# TDFC_V2_0_Black_10by10_1_6mm_ENIG_10pcs.net
KiCad netlist of a schematic drawn in EAGLE
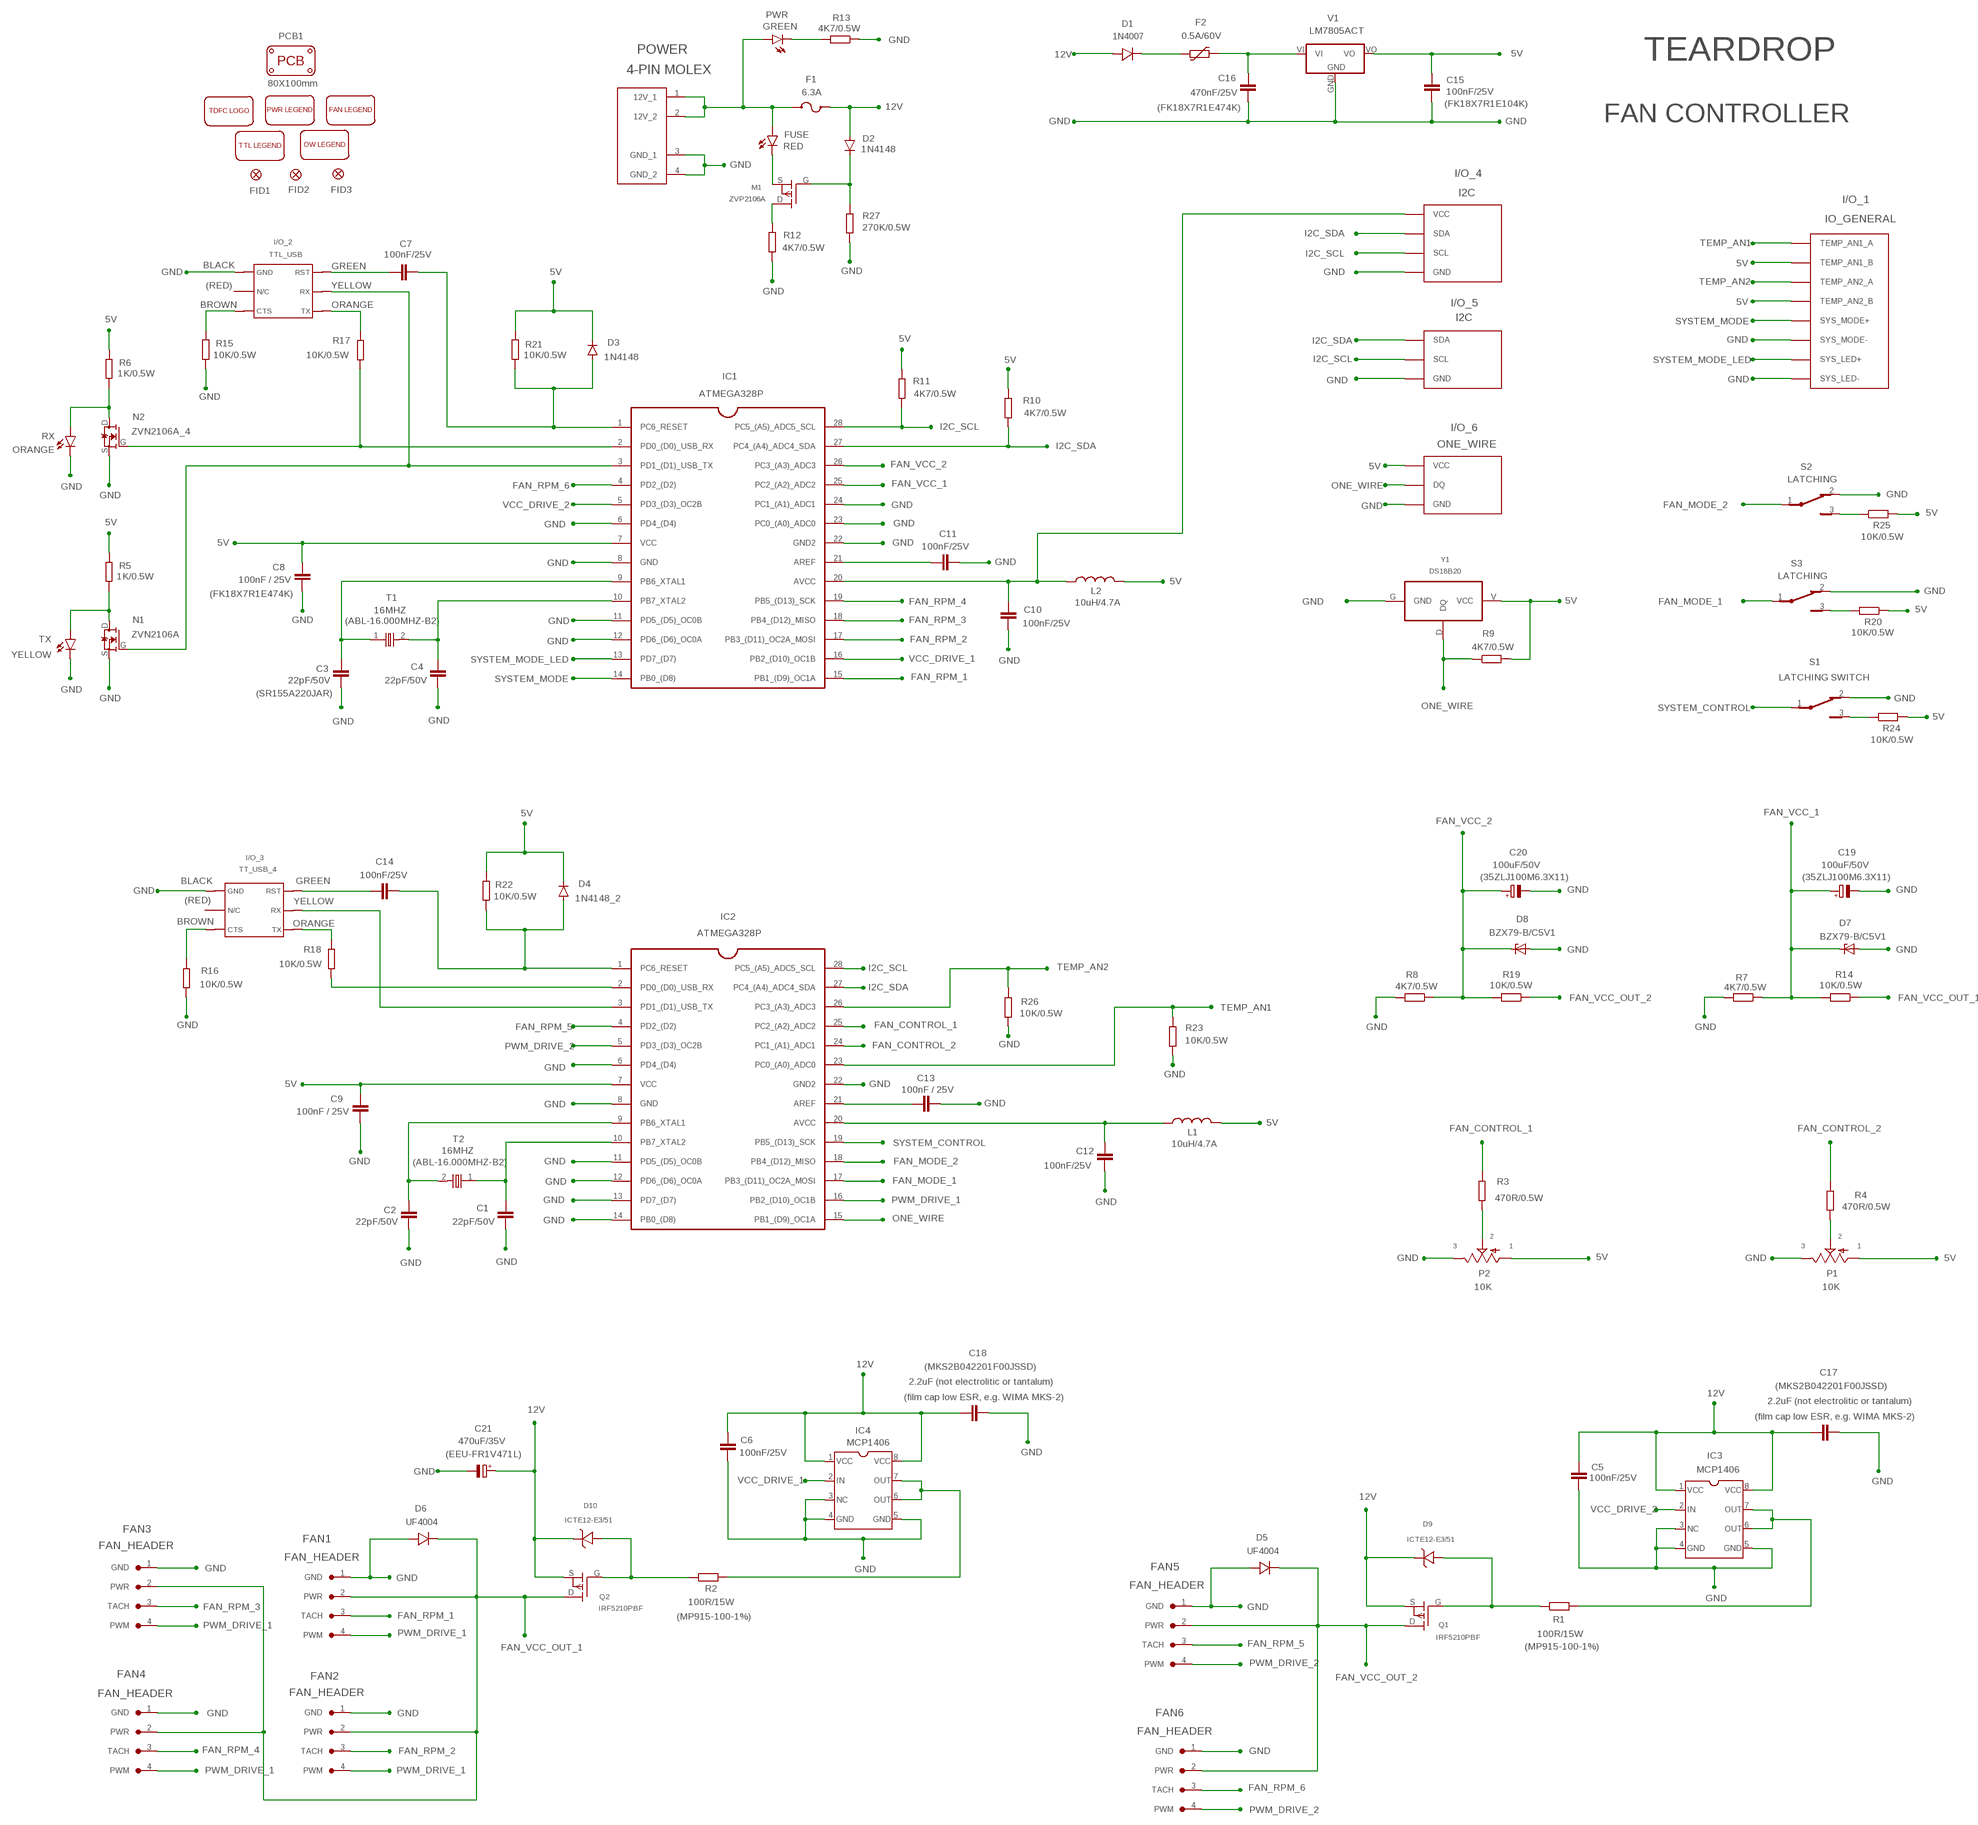
[diagram p0: schematic, sheet 1]

(export (version "E")
  (design (tool "Eeschema 10.0.6"))
  (components
    (comp (ref "C1")
      (value "22pF/50V")
      (footprint "eagle-import:MLCC_CERAMIC_9")
      (libsource (lib "eagle-import") (part "MLCC_CERAMIC_9"))
    )
    (comp (ref "C2")
      (value "22pF/50V")
      (footprint "eagle-import:MLCC_CERAMIC_9")
      (libsource (lib "eagle-import") (part "MLCC_CERAMIC_9"))
    )
    (comp (ref "C3")
      (value "22pF/50V")
      (footprint "eagle-import:MLCC_CERAMIC_11")
      (libsource (lib "eagle-import") (part "MLCC_CERAMIC_11"))
    )
    (comp (ref "C4")
      (value "22pF/50V")
      (footprint "eagle-import:MLCC_CERAMIC_11")
      (libsource (lib "eagle-import") (part "MLCC_CERAMIC_11"))
    )
    (comp (ref "C5")
      (value "100nF/25V")
      (footprint "eagle-import:MLCC_CERAMIC_5")
      (libsource (lib "eagle-import") (part "MLCC_CERAMIC_5"))
    )
    (comp (ref "C6")
      (value "100nF/25V")
      (footprint "eagle-import:MLCC_CERAMIC_5")
      (libsource (lib "eagle-import") (part "MLCC_CERAMIC_5"))
    )
    (comp (ref "C7")
      (value "100nF/25V")
      (footprint "eagle-import:MLCC_CERAMIC_7")
      (libsource (lib "eagle-import") (part "MLCC_CERAMIC_7"))
    )
    (comp (ref "C8")
      (value "100nF / 25V")
      (footprint "eagle-import:MLCC_CERAMIC_5")
      (libsource (lib "eagle-import") (part "MLCC_CERAMIC_5"))
    )
    (comp (ref "C9")
      (value "100nF / 25V")
      (footprint "eagle-import:MLCC_CERAMIC_5")
      (libsource (lib "eagle-import") (part "MLCC_CERAMIC_5"))
    )
    (comp (ref "C10")
      (value "100nF/25V")
      (footprint "eagle-import:MLCC_CERAMIC")
      (libsource (lib "eagle-import") (part "MLCC_CERAMIC"))
    )
    (comp (ref "C11")
      (value "100nF/25V")
      (footprint "eagle-import:MLCC_CERAMIC_17")
      (libsource (lib "eagle-import") (part "MLCC_CERAMIC_17"))
    )
    (comp (ref "C12")
      (value "100nF/25V")
      (footprint "eagle-import:MLCC_CERAMIC_6")
      (libsource (lib "eagle-import") (part "MLCC_CERAMIC_6"))
    )
    (comp (ref "C13")
      (value "100nF / 25V")
      (footprint "eagle-import:MLCC_CERAMIC_6")
      (libsource (lib "eagle-import") (part "MLCC_CERAMIC_6"))
    )
    (comp (ref "C14")
      (value "100nF/25V")
      (footprint "eagle-import:MLCC_CERAMIC_14")
      (libsource (lib "eagle-import") (part "MLCC_CERAMIC_14"))
    )
    (comp (ref "C15")
      (value "100nF/25V")
      (footprint "eagle-import:MLCC_CERAMIC_16")
      (libsource (lib "eagle-import") (part "MLCC_CERAMIC_16"))
    )
    (comp (ref "C16")
      (value "470nF/25V")
      (footprint "eagle-import:MLCC_CERAMIC_15")
      (libsource (lib "eagle-import") (part "MLCC_CERAMIC_15"))
    )
    (comp (ref "C17")
      (value "(MKS2B042201F00JSSD)")
      (footprint "eagle-import:WIMA_CAPACITOR_2")
      (libsource (lib "eagle-import") (part "WIMA_CAPACITOR_2"))
    )
    (comp (ref "C18")
      (value "(MKS2B042201F00JSSD)")
      (footprint "eagle-import:WIMA_CAPACITOR_2")
      (libsource (lib "eagle-import") (part "WIMA_CAPACITOR_2"))
    )
    (comp (ref "C19")
      (value "100uF/50V")
      (footprint "eagle-import:CAPACITOR_6.3_RIGHT")
      (libsource (lib "eagle-import") (part "CAPACITOR_6.3_RIGHT"))
    )
    (comp (ref "C20")
      (value "100uF/50V")
      (footprint "eagle-import:CAPACITOR_6.3_RIGHT")
      (libsource (lib "eagle-import") (part "CAPACITOR_6.3_RIGHT"))
    )
    (comp (ref "C21")
      (value "470uF/35V")
      (footprint "eagle-import:ELECTROLYTIC_CAPACITOR_RIGHT")
      (libsource (lib "eagle-import") (part "ELECTROLYTIC_CAPACITOR_RIGHT"))
    )
    (comp (ref "D1")
      (value "1N4007")
      (footprint "eagle-import:UF4004")
      (libsource (lib "eagle-import") (part "UF4004"))
    )
    (comp (ref "D2")
      (value "1N4148")
      (footprint "eagle-import:1N4148")
      (libsource (lib "eagle-import") (part "1N4148"))
    )
    (comp (ref "D3")
      (value "1N4148")
      (footprint "eagle-import:1N4148")
      (libsource (lib "eagle-import") (part "1N4148"))
    )
    (comp (ref "D4")
      (value "1N4148_2")
      (footprint "eagle-import:1N4148_2")
      (libsource (lib "eagle-import") (part "1N4148_2"))
    )
    (comp (ref "D5")
      (value "UF4004")
      (footprint "eagle-import:UF4004_2")
      (libsource (lib "eagle-import") (part "UF4004_2"))
    )
    (comp (ref "D6")
      (value "UF4004")
      (footprint "eagle-import:UF4004_2")
      (libsource (lib "eagle-import") (part "UF4004_2"))
    )
    (comp (ref "D7")
      (value "BZX79-B/C5V1")
      (footprint "eagle-import:DO34_2")
      (libsource (lib "eagle-import") (part "BZX90_2"))
    )
    (comp (ref "D8")
      (value "BZX79-B/C5V1")
      (footprint "eagle-import:DO34Z7")
      (libsource (lib "eagle-import") (part "BZX90"))
    )
    (comp (ref "D9")
      (value "ICTE12-E3/51")
      (footprint "eagle-import:TVS_DIODE_5")
      (libsource (lib "eagle-import") (part "TVS_DIODE_5"))
    )
    (comp (ref "D10")
      (value "ICTE12-E3/51")
      (footprint "eagle-import:TVS_DIODE_5")
      (libsource (lib "eagle-import") (part "TVS_DIODE_5"))
    )
    (comp (ref "F1")
      (value "6.3A")
      (footprint "eagle-import:FUSE_GLASS")
      (libsource (lib "eagle-import") (part "FUSE_GLASS"))
    )
    (comp (ref "F2")
      (value "0.5A/60V")
      (footprint "eagle-import:PTC")
      (libsource (lib "eagle-import") (part "PTC"))
    )
    (comp (ref "FAN1")
      (value "FAN_HEADER")
      (footprint "eagle-import:4PIN_FAN_HEADER")
      (libsource (lib "eagle-import") (part "4PIN_FAN_HEADER"))
    )
    (comp (ref "FAN2")
      (value "FAN_HEADER")
      (footprint "eagle-import:4PIN_FAN_HEADER")
      (libsource (lib "eagle-import") (part "4PIN_FAN_HEADER"))
    )
    (comp (ref "FAN3")
      (value "FAN_HEADER")
      (footprint "eagle-import:4PIN_FAN_HEADER")
      (libsource (lib "eagle-import") (part "4PIN_FAN_HEADER"))
    )
    (comp (ref "FAN4")
      (value "FAN_HEADER")
      (footprint "eagle-import:4PIN_FAN_HEADER")
      (libsource (lib "eagle-import") (part "4PIN_FAN_HEADER"))
    )
    (comp (ref "FAN5")
      (value "FAN_HEADER")
      (footprint "eagle-import:4PIN_FAN_HEADER")
      (libsource (lib "eagle-import") (part "4PIN_FAN_HEADER"))
    )
    (comp (ref "FAN6")
      (value "FAN_HEADER")
      (footprint "eagle-import:4PIN_FAN_HEADER")
      (libsource (lib "eagle-import") (part "4PIN_FAN_HEADER"))
    )
    (comp (ref "FID1")
      (value "FIDUCIAL1X2")
      (footprint "eagle-import:FIDUCIAL-1X2")
      (libsource (lib "eagle-import") (part "FIDUCIAL1X2"))
    )
    (comp (ref "FID2")
      (value "FIDUCIAL1X2")
      (footprint "eagle-import:FIDUCIAL-1X2")
      (libsource (lib "eagle-import") (part "FIDUCIAL1X2"))
    )
    (comp (ref "FID3")
      (value "FIDUCIAL1X2")
      (footprint "eagle-import:FIDUCIAL-1X2")
      (libsource (lib "eagle-import") (part "FIDUCIAL1X2"))
    )
    (comp (ref "FUSE")
      (value "RED")
      (footprint "eagle-import:LED_1.8_LEFT")
      (libsource (lib "eagle-import") (part "LED_1.8_LEFT"))
    )
    (comp (ref "I/O_1")
      (value "IO_GENERAL")
      (footprint "eagle-import:IO_GENERAL_7")
      (libsource (lib "eagle-import") (part "IO_GENERAL_7"))
    )
    (comp (ref "I/O_2")
      (value "TTL_USB")
      (footprint "eagle-import:TTL_USB_5")
      (libsource (lib "eagle-import") (part "TTL_USB_5"))
    )
    (comp (ref "I/O_3")
      (value "TT_USB_4")
      (footprint "eagle-import:TT_USB_4")
      (libsource (lib "eagle-import") (part "TT_USB_4"))
    )
    (comp (ref "I/O_4")
      (value "I2C")
      (footprint "eagle-import:4_PIN_HEADER_VERTICAL_2")
      (libsource (lib "eagle-import") (part "4_PIN_HEADER_VERTICAL_2"))
    )
    (comp (ref "I/O_5")
      (value "I2C")
      (footprint "eagle-import:3_PIN_VERTICAL_4")
      (libsource (lib "eagle-import") (part "3_PIN_VERTICAL_4"))
    )
    (comp (ref "I/O_6")
      (value "ONE_WIRE")
      (footprint "eagle-import:3_PIN_VERTICAL")
      (libsource (lib "eagle-import") (part "3_PIN_VERTICAL"))
    )
    (comp (ref "IC1")
      (value "ATMEGA328P")
      (footprint "eagle-import:ATMEGA328P")
      (libsource (lib "eagle-import") (part "ATMEGA328P"))
    )
    (comp (ref "IC2")
      (value "ATMEGA328P")
      (footprint "eagle-import:ATMEGA328P_2")
      (libsource (lib "eagle-import") (part "ATMEGA328P_VER_2.0"))
    )
    (comp (ref "IC3")
      (value "MCP1406")
      (footprint "eagle-import:TC4420")
      (libsource (lib "eagle-import") (part "TC4420"))
    )
    (comp (ref "IC4")
      (value "MCP1406")
      (footprint "eagle-import:TC4420")
      (libsource (lib "eagle-import") (part "TC4420"))
    )
    (comp (ref "L1")
      (value "10uH/4.7A")
      (footprint "eagle-import:INDUCTOR")
      (libsource (lib "eagle-import") (part "INDUCTOR"))
    )
    (comp (ref "L2")
      (value "10uH/4.7A")
      (footprint "eagle-import:INDUCTOR")
      (libsource (lib "eagle-import") (part "INDUCTOR"))
    )
    (comp (ref "M1")
      (value "ZVP2106A")
      (footprint "eagle-import:ZVP2106A")
      (libsource (lib "eagle-import") (part "ZVP2106A"))
    )
    (comp (ref "N1")
      (value "ZVN2106A")
      (footprint "eagle-import:ZVN2106A")
      (libsource (lib "eagle-import") (part "ZVN2106A"))
    )
    (comp (ref "N2")
      (value "ZVN2106A_4")
      (footprint "eagle-import:ZVN2106A_4")
      (libsource (lib "eagle-import") (part "ZVN2106A_4"))
    )
    (comp (ref "P1")
      (value "10K")
      (footprint "eagle-import:POTENTIMETER_SQUARE")
      (libsource (lib "eagle-import") (part "POTENTIMETER_SQUARE"))
    )
    (comp (ref "P2")
      (value "10K")
      (footprint "eagle-import:POTENTIMETER_SQUARE")
      (libsource (lib "eagle-import") (part "POTENTIMETER_SQUARE"))
    )
    (comp (ref "PCB1")
      (value "80X100mm")
      (footprint "eagle-import:DP10080_V1")
      (libsource (lib "eagle-import") (part "PCB_DP_RECTANGLE-80X100"))
    )
    (comp (ref "POWER")
      (value "4-PIN MOLEX")
      (footprint "eagle-import:MOLEX_4PIN_2")
      (libsource (lib "eagle-import") (part "MOLEX_4PIN_2"))
    )
    (comp (ref "PWR")
      (value "GREEN")
      (footprint "eagle-import:LED_1.8_LEFT")
      (libsource (lib "eagle-import") (part "LED_1.8_LEFT"))
    )
    (comp (ref "Q1")
      (value "IRF5210PBF")
      (footprint "eagle-import:IRF5210")
      (libsource (lib "eagle-import") (part "IRF5210"))
    )
    (comp (ref "Q2")
      (value "IRF5210PBF")
      (footprint "eagle-import:IRF5210")
      (libsource (lib "eagle-import") (part "IRF5210"))
    )
    (comp (ref "R1")
      (value "100R/15W")
      (footprint "eagle-import:V234_12")
      (libsource (lib "eagle-import") (part "R-EU_V234/12"))
    )
    (comp (ref "R2")
      (value "100R/15W")
      (footprint "eagle-import:V234_12")
      (libsource (lib "eagle-import") (part "R-EU_V234/12"))
    )
    (comp (ref "R3")
      (value "470R/0.5W")
      (footprint "eagle-import:0204_5")
      (libsource (lib "eagle-import") (part "RESISTOR (REGULAR, 0.25W)_R-EU_0204/5"))
    )
    (comp (ref "R4")
      (value "470R/0.5W")
      (footprint "eagle-import:0204_5")
      (libsource (lib "eagle-import") (part "RESISTOR (REGULAR, 0.25W)_R-EU_0204/5"))
    )
    (comp (ref "R5")
      (value "1K/0.5W")
      (footprint "eagle-import:0204_5")
      (libsource (lib "eagle-import") (part "RESISTOR (REGULAR, 0.25W)_R-EU_0204/5"))
    )
    (comp (ref "R6")
      (value "1K/0.5W")
      (footprint "eagle-import:0204_5")
      (libsource (lib "eagle-import") (part "RESISTOR (REGULAR, 0.25W)_R-EU_0204/5"))
    )
    (comp (ref "R7")
      (value "4K7/0.5W")
      (footprint "eagle-import:0204_5")
      (libsource (lib "eagle-import") (part "RESISTOR (REGULAR, 0.25W)_R-EU_0204/5"))
    )
    (comp (ref "R8")
      (value "4K7/0.5W")
      (footprint "eagle-import:0204_5")
      (libsource (lib "eagle-import") (part "RESISTOR (REGULAR, 0.25W)_R-EU_0204/5"))
    )
    (comp (ref "R9")
      (value "4K7/0.5W")
      (footprint "eagle-import:0204_5")
      (libsource (lib "eagle-import") (part "RESISTOR (REGULAR, 0.25W)_R-EU_0204/5"))
    )
    (comp (ref "R10")
      (value "4K7/0.5W")
      (footprint "eagle-import:0204_5")
      (libsource (lib "eagle-import") (part "RESISTOR (REGULAR, 0.25W)_R-EU_0204/5"))
    )
    (comp (ref "R11")
      (value "4K7/0.5W")
      (footprint "eagle-import:0204_5")
      (libsource (lib "eagle-import") (part "RESISTOR (REGULAR, 0.25W)_R-EU_0204/5"))
    )
    (comp (ref "R12")
      (value "4K7/0.5W")
      (footprint "eagle-import:0204_5")
      (libsource (lib "eagle-import") (part "RESISTOR (REGULAR, 0.25W)_R-EU_0204/5"))
    )
    (comp (ref "R13")
      (value "4K7/0.5W")
      (footprint "eagle-import:0204_5")
      (libsource (lib "eagle-import") (part "RESISTOR (REGULAR, 0.25W)_R-EU_0204/5"))
    )
    (comp (ref "R14")
      (value "10K/0.5W")
      (footprint "eagle-import:0204_5")
      (libsource (lib "eagle-import") (part "RESISTOR (REGULAR, 0.25W)_R-EU_0204/5"))
    )
    (comp (ref "R15")
      (value "10K/0.5W")
      (footprint "eagle-import:0204_5")
      (libsource (lib "eagle-import") (part "RESISTOR (REGULAR, 0.25W)_R-EU_0204/5"))
    )
    (comp (ref "R16")
      (value "10K/0.5W")
      (footprint "eagle-import:0204_5")
      (libsource (lib "eagle-import") (part "RESISTOR (REGULAR, 0.25W)_R-EU_0204/5"))
    )
    (comp (ref "R17")
      (value "10K/0.5W")
      (footprint "eagle-import:0204_5")
      (libsource (lib "eagle-import") (part "RESISTOR (REGULAR, 0.25W)_R-EU_0204/5"))
    )
    (comp (ref "R18")
      (value "10K/0.5W")
      (footprint "eagle-import:0204_5")
      (libsource (lib "eagle-import") (part "RESISTOR (REGULAR, 0.25W)_R-EU_0204/5"))
    )
    (comp (ref "R19")
      (value "10K/0.5W")
      (footprint "eagle-import:0204_5")
      (libsource (lib "eagle-import") (part "RESISTOR (REGULAR, 0.25W)_R-EU_0204/5"))
    )
    (comp (ref "R20")
      (value "10K/0.5W")
      (footprint "eagle-import:0204_5")
      (libsource (lib "eagle-import") (part "RESISTOR (REGULAR, 0.25W)_R-EU_0204/5"))
    )
    (comp (ref "R21")
      (value "10K/0.5W")
      (footprint "eagle-import:0204_5")
      (libsource (lib "eagle-import") (part "RESISTOR (REGULAR, 0.25W)_R-EU_0204/5"))
    )
    (comp (ref "R22")
      (value "10K/0.5W")
      (footprint "eagle-import:0204_5")
      (libsource (lib "eagle-import") (part "RESISTOR (REGULAR, 0.25W)_R-EU_0204/5"))
    )
    (comp (ref "R23")
      (value "10K/0.5W")
      (footprint "eagle-import:0204_5")
      (libsource (lib "eagle-import") (part "RESISTOR (REGULAR, 0.25W)_R-EU_0204/5"))
    )
    (comp (ref "R24")
      (value "10K/0.5W")
      (footprint "eagle-import:0204_5")
      (libsource (lib "eagle-import") (part "RESISTOR (REGULAR, 0.25W)_R-EU_0204/5"))
    )
    (comp (ref "R25")
      (value "10K/0.5W")
      (footprint "eagle-import:0204_5")
      (libsource (lib "eagle-import") (part "RESISTOR (REGULAR, 0.25W)_R-EU_0204/5"))
    )
    (comp (ref "R26")
      (value "10K/0.5W")
      (footprint "eagle-import:0204_5")
      (libsource (lib "eagle-import") (part "RESISTOR (REGULAR, 0.25W)_R-EU_0204/5"))
    )
    (comp (ref "R27")
      (value "270K/0.5W")
      (footprint "eagle-import:0204_5")
      (libsource (lib "eagle-import") (part "RESISTOR (REGULAR, 0.25W)_R-EU_0204/5"))
    )
    (comp (ref "RX")
      (value "ORANGE")
      (footprint "eagle-import:LED_1.8_LEFT_2")
      (libsource (lib "eagle-import") (part "LED_1.8_LEFT_2"))
    )
    (comp (ref "S1")
      (value "LATCHING SWITCH")
      (footprint "eagle-import:SLIDING_SWITCH_4")
      (libsource (lib "eagle-import") (part "SLIDING_SWITCH_4"))
    )
    (comp (ref "S2")
      (value "LATCHING")
      (footprint "eagle-import:SLIDING_SWITCH_5")
      (libsource (lib "eagle-import") (part "SLIDING_SWITCH_5"))
    )
    (comp (ref "S3")
      (value "LATCHING")
      (footprint "eagle-import:SLIDING_SWITCH_5")
      (libsource (lib "eagle-import") (part "SLIDING_SWITCH_5"))
    )
    (comp (ref "T1")
      (value "16MHZ")
      (footprint "eagle-import:CRYSTAL_16MHZ")
      (libsource (lib "eagle-import") (part "CRYSTAL_16MHZ"))
    )
    (comp (ref "T2")
      (value "16MHZ")
      (footprint "eagle-import:CRYSTAL_16MHZ")
      (libsource (lib "eagle-import") (part "CRYSTAL_16MHZ"))
    )
    (comp (ref "TX")
      (value "YELLOW")
      (footprint "eagle-import:LED_1.8_LEFT_2")
      (libsource (lib "eagle-import") (part "LED_1.8_LEFT_2"))
    )
    (comp (ref "U$1")
      (value "TDFC_LOGO")
      (footprint "eagle-import:TDFC_LOGO")
      (libsource (lib "eagle-import") (part "TDFC_LOGO"))
    )
    (comp (ref "U$2")
      (value "MOLEX_4PIN_LEGEND_2")
      (footprint "eagle-import:MOLEX_4PIN_LEGEND_2")
      (libsource (lib "eagle-import") (part "MOLEX_4PIN_LEGEND_2"))
    )
    (comp (ref "U$3")
      (value "FAN_HEADER_LEGEND")
      (footprint "eagle-import:FAN_HEADER_LEGEND")
      (libsource (lib "eagle-import") (part "FAN_HEADER_LEGEND"))
    )
    (comp (ref "U$4")
      (value "TTL_USB_6")
      (footprint "eagle-import:TTL_USB_6")
      (libsource (lib "eagle-import") (part "TTL_USB_6"))
    )
    (comp (ref "U$5")
      (value "3_PIN_VERTICAL_LEGEND")
      (footprint "eagle-import:3_PIN_VERTICAL_LEGEND")
      (libsource (lib "eagle-import") (part "3_PIN_VERTICAL_LEGEND"))
    )
    (comp (ref "V1")
      (value "LM7805ACT")
      (footprint "eagle-import:LM7805")
      (libsource (lib "eagle-import") (part "LM7805"))
    )
    (comp (ref "Y1")
      (value "DS18B20")
      (footprint "eagle-import:DS18B20")
      (libsource (lib "eagle-import") (part "DS18B20"))
    )
  )
  (nets
    (net (code "1") (name "/5V") (class "Default")
      (node (ref "C15") (pin "2") (pinfunction "2_2") (pintype "passive"))
      (node (ref "C8") (pin "1") (pinfunction "1_1") (pintype "passive"))
      (node (ref "C9") (pin "1") (pinfunction "1_1") (pintype "passive"))
      (node (ref "D3") (pin "C") (pinfunction "C_C") (pintype "passive"))
      (node (ref "D4") (pin "C") (pinfunction "C_C") (pintype "passive"))
      (node (ref "I/O_1") (pin "TEMP_AN1_B") (pinfunction "TEMP_AN1_B_TEMP_AN1_B") (pintype "passive"))
      (node (ref "I/O_1") (pin "TEMP_AN2_B") (pinfunction "TEMP_AN2_B_TEMP_AN2_B") (pintype "passive"))
      (node (ref "I/O_6") (pin "VCC") (pinfunction "VCC_VCC") (pintype "passive"))
      (node (ref "IC1") (pin "7") (pinfunction "VCC_7") (pintype "bidirectional"))
      (node (ref "IC2") (pin "7") (pinfunction "VCC_7") (pintype "bidirectional"))
      (node (ref "L1") (pin "2") (pinfunction "2_2") (pintype "passive"))
      (node (ref "L2") (pin "2") (pinfunction "2_2") (pintype "passive"))
      (node (ref "P1") (pin "1") (pinfunction "A_1") (pintype "passive"))
      (node (ref "P2") (pin "1") (pinfunction "A_1") (pintype "passive"))
      (node (ref "R10") (pin "1") (pinfunction "1_1") (pintype "passive"))
      (node (ref "R11") (pin "1") (pinfunction "1_1") (pintype "passive"))
      (node (ref "R20") (pin "1") (pinfunction "1_1") (pintype "passive"))
      (node (ref "R21") (pin "2") (pinfunction "2_2") (pintype "passive"))
      (node (ref "R22") (pin "2") (pinfunction "2_2") (pintype "passive"))
      (node (ref "R24") (pin "2") (pinfunction "2_2") (pintype "passive"))
      (node (ref "R25") (pin "2") (pinfunction "2_2") (pintype "passive"))
      (node (ref "R5") (pin "2") (pinfunction "2_2") (pintype "passive"))
      (node (ref "R6") (pin "2") (pinfunction "2_2") (pintype "passive"))
      (node (ref "R9") (pin "2") (pinfunction "2_2") (pintype "passive"))
      (node (ref "V1") (pin "VO") (pinfunction "VO_VO") (pintype "passive"))
      (node (ref "Y1") (pin "V") (pinfunction "VCC_V") (pintype "passive"))
    )
    (net (code "2") (name "/12V") (class "Default")
      (node (ref "C17") (pin "1") (pinfunction "1_1") (pintype "passive"))
      (node (ref "C18") (pin "1") (pinfunction "1_1") (pintype "passive"))
      (node (ref "C21") (pin "+") (pinfunction "+_+") (pintype "passive"))
      (node (ref "C5") (pin "2") (pinfunction "2_2") (pintype "passive"))
      (node (ref "C6") (pin "2") (pinfunction "2_2") (pintype "passive"))
      (node (ref "D1") (pin "A") (pinfunction "A_A") (pintype "passive"))
      (node (ref "D10") (pin "C") (pinfunction "C_C") (pintype "passive"))
      (node (ref "D2") (pin "A") (pinfunction "A_A") (pintype "passive"))
      (node (ref "D9") (pin "C") (pinfunction "C_C") (pintype "passive"))
      (node (ref "F1") (pin "2") (pinfunction "2_2") (pintype "passive"))
      (node (ref "IC3") (pin "1") (pinfunction "1_1") (pintype "passive"))
      (node (ref "IC3") (pin "8") (pinfunction "8_8") (pintype "passive"))
      (node (ref "IC4") (pin "1") (pinfunction "1_1") (pintype "passive"))
      (node (ref "IC4") (pin "8") (pinfunction "8_8") (pintype "passive"))
      (node (ref "Q1") (pin "S") (pinfunction "S_S") (pintype "passive"))
      (node (ref "Q2") (pin "S") (pinfunction "S_S") (pintype "passive"))
    )
    (net (code "3") (name "/FAN_CONTROL_1") (class "Default")
      (node (ref "IC2") (pin "25") (pinfunction "PC2_(A2)_ADC2_25") (pintype "bidirectional"))
      (node (ref "R3") (pin "1") (pinfunction "1_1") (pintype "passive"))
    )
    (net (code "4") (name "/FAN_CONTROL_2") (class "Default")
      (node (ref "IC2") (pin "24") (pinfunction "PC1_(A1)_ADC1_24") (pintype "bidirectional"))
      (node (ref "R4") (pin "1") (pinfunction "1_1") (pintype "passive"))
    )
    (net (code "5") (name "/FAN_MODE_1") (class "Default")
      (node (ref "IC2") (pin "17") (pinfunction "PB3_(D11)_OC2A_MOSI_17") (pintype "bidirectional"))
      (node (ref "S3") (pin "1") (pinfunction "1_1") (pintype "passive"))
    )
    (net (code "6") (name "/FAN_MODE_2") (class "Default")
      (node (ref "IC2") (pin "18") (pinfunction "PB4_(D12)_MISO_18") (pintype "bidirectional"))
      (node (ref "S2") (pin "1") (pinfunction "1_1") (pintype "passive"))
    )
    (net (code "7") (name "/FAN_RPM_1") (class "Default")
      (node (ref "FAN1") (pin "3") (pinfunction "TACH_3") (pintype "passive"))
      (node (ref "IC1") (pin "15") (pinfunction "PB1_(D9)_OC1A_15") (pintype "bidirectional"))
    )
    (net (code "8") (name "/FAN_RPM_2") (class "Default")
      (node (ref "FAN2") (pin "3") (pinfunction "TACH_3") (pintype "passive"))
      (node (ref "IC1") (pin "17") (pinfunction "PB3_(D11)_OC2A_MOSI_17") (pintype "bidirectional"))
    )
    (net (code "9") (name "/FAN_RPM_3") (class "Default")
      (node (ref "FAN3") (pin "3") (pinfunction "TACH_3") (pintype "passive"))
      (node (ref "IC1") (pin "18") (pinfunction "PB4_(D12)_MISO_18") (pintype "bidirectional"))
    )
    (net (code "10") (name "/FAN_RPM_4") (class "Default")
      (node (ref "FAN4") (pin "3") (pinfunction "TACH_3") (pintype "passive"))
      (node (ref "IC1") (pin "19") (pinfunction "PB5_(D13)_SCK_19") (pintype "bidirectional"))
    )
    (net (code "11") (name "/FAN_RPM_5") (class "Default")
      (node (ref "FAN5") (pin "3") (pinfunction "TACH_3") (pintype "passive"))
      (node (ref "IC2") (pin "4") (pinfunction "PD2_(D2)_4") (pintype "bidirectional"))
    )
    (net (code "12") (name "/FAN_RPM_6") (class "Default")
      (node (ref "FAN6") (pin "3") (pinfunction "TACH_3") (pintype "passive"))
      (node (ref "IC1") (pin "4") (pinfunction "PD2_(D2)_4") (pintype "bidirectional"))
    )
    (net (code "13") (name "/FAN_VCC_1") (class "Default")
      (node (ref "C19") (pin "+") (pinfunction "+_+") (pintype "passive"))
      (node (ref "D7") (pin "C") (pinfunction "C_C") (pintype "passive"))
      (node (ref "IC1") (pin "25") (pinfunction "PC2_(A2)_ADC2_25") (pintype "bidirectional"))
      (node (ref "R14") (pin "2") (pinfunction "2_2") (pintype "passive"))
      (node (ref "R7") (pin "1") (pinfunction "1_1") (pintype "passive"))
    )
    (net (code "14") (name "/FAN_VCC_2") (class "Default")
      (node (ref "C20") (pin "+") (pinfunction "+_+") (pintype "passive"))
      (node (ref "D8") (pin "C") (pinfunction "C_C") (pintype "passive"))
      (node (ref "IC1") (pin "26") (pinfunction "PC3_(A3)_ADC3_26") (pintype "bidirectional"))
      (node (ref "R19") (pin "2") (pinfunction "2_2") (pintype "passive"))
      (node (ref "R8") (pin "1") (pinfunction "1_1") (pintype "passive"))
    )
    (net (code "15") (name "/FAN_VCC_OUT_1") (class "Default")
      (node (ref "D6") (pin "C") (pinfunction "C_C") (pintype "passive"))
      (node (ref "FAN1") (pin "2") (pinfunction "PWR_2") (pintype "passive"))
      (node (ref "FAN2") (pin "2") (pinfunction "PWR_2") (pintype "passive"))
      (node (ref "FAN3") (pin "2") (pinfunction "PWR_2") (pintype "passive"))
      (node (ref "FAN4") (pin "2") (pinfunction "PWR_2") (pintype "passive"))
      (node (ref "Q2") (pin "D") (pinfunction "D_D") (pintype "passive"))
      (node (ref "R14") (pin "1") (pinfunction "1_1") (pintype "passive"))
    )
    (net (code "16") (name "/FAN_VCC_OUT_2") (class "Default")
      (node (ref "D5") (pin "C") (pinfunction "C_C") (pintype "passive"))
      (node (ref "FAN5") (pin "2") (pinfunction "PWR_2") (pintype "passive"))
      (node (ref "FAN6") (pin "2") (pinfunction "PWR_2") (pintype "passive"))
      (node (ref "Q1") (pin "D") (pinfunction "D_D") (pintype "passive"))
      (node (ref "R19") (pin "1") (pinfunction "1_1") (pintype "passive"))
    )
    (net (code "17") (name "/GND") (class "Default")
      (node (ref "C1") (pin "2") (pinfunction "2_2") (pintype "passive"))
      (node (ref "C10") (pin "2") (pinfunction "2_2") (pintype "passive"))
      (node (ref "C11") (pin "2") (pinfunction "2_2") (pintype "passive"))
      (node (ref "C12") (pin "2") (pinfunction "2_2") (pintype "passive"))
      (node (ref "C13") (pin "2") (pinfunction "2_2") (pintype "passive"))
      (node (ref "C15") (pin "1") (pinfunction "1_1") (pintype "passive"))
      (node (ref "C16") (pin "2") (pinfunction "2_2") (pintype "passive"))
      (node (ref "C17") (pin "2") (pinfunction "2_2") (pintype "passive"))
      (node (ref "C18") (pin "2") (pinfunction "2_2") (pintype "passive"))
      (node (ref "C19") (pin "-") (pinfunction "-_-") (pintype "passive"))
      (node (ref "C2") (pin "2") (pinfunction "2_2") (pintype "passive"))
      (node (ref "C20") (pin "-") (pinfunction "-_-") (pintype "passive"))
      (node (ref "C21") (pin "-") (pinfunction "-_-") (pintype "passive"))
      (node (ref "C3") (pin "2") (pinfunction "2_2") (pintype "passive"))
      (node (ref "C4") (pin "2") (pinfunction "2_2") (pintype "passive"))
      (node (ref "C5") (pin "1") (pinfunction "1_1") (pintype "passive"))
      (node (ref "C6") (pin "1") (pinfunction "1_1") (pintype "passive"))
      (node (ref "C8") (pin "2") (pinfunction "2_2") (pintype "passive"))
      (node (ref "C9") (pin "2") (pinfunction "2_2") (pintype "passive"))
      (node (ref "D5") (pin "A") (pinfunction "A_A") (pintype "passive"))
      (node (ref "D6") (pin "A") (pinfunction "A_A") (pintype "passive"))
      (node (ref "D7") (pin "A") (pinfunction "A_A") (pintype "passive"))
      (node (ref "D8") (pin "A") (pinfunction "A_A") (pintype "passive"))
      (node (ref "FAN1") (pin "1") (pinfunction "GND_1") (pintype "passive"))
      (node (ref "FAN2") (pin "1") (pinfunction "GND_1") (pintype "passive"))
      (node (ref "FAN3") (pin "1") (pinfunction "GND_1") (pintype "passive"))
      (node (ref "FAN4") (pin "1") (pinfunction "GND_1") (pintype "passive"))
      (node (ref "FAN5") (pin "1") (pinfunction "GND_1") (pintype "passive"))
      (node (ref "FAN6") (pin "1") (pinfunction "GND_1") (pintype "passive"))
      (node (ref "I/O_1") (pin "SYSTEM_LED-") (pinfunction "SYS_LED-_SYSTEM_LED-") (pintype "passive"))
      (node (ref "I/O_1") (pin "SYSTEM_MODE-") (pinfunction "SYS_MODE-_SYSTEM_MODE-") (pintype "passive"))
      (node (ref "I/O_2") (pin "GND") (pinfunction "GND_GND") (pintype "passive"))
      (node (ref "I/O_3") (pin "GND") (pinfunction "GND_GND") (pintype "passive"))
      (node (ref "I/O_4") (pin "GND") (pinfunction "GND_GND") (pintype "passive"))
      (node (ref "I/O_5") (pin "GND") (pinfunction "GND_GND") (pintype "passive"))
      (node (ref "I/O_6") (pin "GND") (pinfunction "GND_GND") (pintype "passive"))
      (node (ref "IC1") (pin "11") (pinfunction "PD5_(D5)_OC0B_11") (pintype "bidirectional"))
      (node (ref "IC1") (pin "12") (pinfunction "PD6_(D6)_OC0A_12") (pintype "bidirectional"))
      (node (ref "IC1") (pin "22") (pinfunction "GND2_22") (pintype "bidirectional"))
      (node (ref "IC1") (pin "23") (pinfunction "PC0_(A0)_ADC0_23") (pintype "bidirectional"))
      (node (ref "IC1") (pin "24") (pinfunction "PC1_(A1)_ADC1_24") (pintype "bidirectional"))
      (node (ref "IC1") (pin "6") (pinfunction "PD4_(D4)_6") (pintype "bidirectional"))
      (node (ref "IC1") (pin "8") (pinfunction "GND_8") (pintype "bidirectional"))
      (node (ref "IC2") (pin "11") (pinfunction "PD5_(D5)_OC0B_11") (pintype "bidirectional"))
      (node (ref "IC2") (pin "12") (pinfunction "PD6_(D6)_OC0A_12") (pintype "bidirectional"))
      (node (ref "IC2") (pin "13") (pinfunction "PD7_(D7)_13") (pintype "bidirectional"))
      (node (ref "IC2") (pin "14") (pinfunction "PB0_(D8)_14") (pintype "bidirectional"))
      (node (ref "IC2") (pin "22") (pinfunction "GND2_22") (pintype "bidirectional"))
      (node (ref "IC2") (pin "6") (pinfunction "PD4_(D4)_6") (pintype "bidirectional"))
      (node (ref "IC2") (pin "8") (pinfunction "GND_8") (pintype "bidirectional"))
      (node (ref "IC3") (pin "3") (pinfunction "3_3") (pintype "passive"))
      (node (ref "IC3") (pin "4") (pinfunction "4_4") (pintype "passive"))
      (node (ref "IC3") (pin "5") (pinfunction "5_5") (pintype "passive"))
      (node (ref "IC4") (pin "3") (pinfunction "3_3") (pintype "passive"))
      (node (ref "IC4") (pin "4") (pinfunction "4_4") (pintype "passive"))
      (node (ref "IC4") (pin "5") (pinfunction "5_5") (pintype "passive"))
      (node (ref "N1") (pin "S") (pinfunction "S_S") (pintype "passive"))
      (node (ref "N2") (pin "S") (pinfunction "S_S") (pintype "passive"))
      (node (ref "P1") (pin "3") (pinfunction "E_3") (pintype "passive"))
      (node (ref "P2") (pin "3") (pinfunction "E_3") (pintype "passive"))
      (node (ref "POWER") (pin "3") (pinfunction "GND_1_3") (pintype "passive"))
      (node (ref "POWER") (pin "4") (pinfunction "GND_2_4") (pintype "passive"))
      (node (ref "R12") (pin "1") (pinfunction "1_1") (pintype "passive"))
      (node (ref "R13") (pin "1") (pinfunction "1_1") (pintype "passive"))
      (node (ref "R15") (pin "1") (pinfunction "1_1") (pintype "passive"))
      (node (ref "R16") (pin "2") (pinfunction "2_2") (pintype "passive"))
      (node (ref "R23") (pin "2") (pinfunction "2_2") (pintype "passive"))
      (node (ref "R26") (pin "2") (pinfunction "2_2") (pintype "passive"))
      (node (ref "R27") (pin "2") (pinfunction "2_2") (pintype "passive"))
      (node (ref "R7") (pin "2") (pinfunction "2_2") (pintype "passive"))
      (node (ref "R8") (pin "2") (pinfunction "2_2") (pintype "passive"))
      (node (ref "RX") (pin "K") (pinfunction "C_K") (pintype "passive"))
      (node (ref "S1") (pin "2") (pinfunction "2_2") (pintype "passive"))
      (node (ref "S2") (pin "2") (pinfunction "2_2") (pintype "passive"))
      (node (ref "S3") (pin "2") (pinfunction "2_2") (pintype "passive"))
      (node (ref "TX") (pin "K") (pinfunction "C_K") (pintype "passive"))
      (node (ref "V1") (pin "GND") (pinfunction "GND_GND") (pintype "passive"))
      (node (ref "Y1") (pin "G") (pinfunction "GND_G") (pintype "passive"))
    )
    (net (code "18") (name "/I2C_SCL") (class "Default")
      (node (ref "I/O_4") (pin "SCL") (pinfunction "SCL_SCL") (pintype "passive"))
      (node (ref "I/O_5") (pin "SCL") (pinfunction "SCL_SCL") (pintype "passive"))
      (node (ref "IC1") (pin "28") (pinfunction "PC5_(A5)_ADC5_SCL_28") (pintype "bidirectional"))
      (node (ref "IC2") (pin "28") (pinfunction "PC5_(A5)_ADC5_SCL_28") (pintype "bidirectional"))
      (node (ref "R11") (pin "2") (pinfunction "2_2") (pintype "passive"))
    )
    (net (code "19") (name "/I2C_SDA") (class "Default")
      (node (ref "I/O_4") (pin "SDA") (pinfunction "SDA_SDA") (pintype "passive"))
      (node (ref "I/O_5") (pin "SDA") (pinfunction "SDA_SDA") (pintype "passive"))
      (node (ref "IC1") (pin "27") (pinfunction "PC4_(A4)_ADC4_SDA_27") (pintype "bidirectional"))
      (node (ref "IC2") (pin "27") (pinfunction "PC4_(A4)_ADC4_SDA_27") (pintype "bidirectional"))
      (node (ref "R10") (pin "2") (pinfunction "2_2") (pintype "passive"))
    )
    (net (code "20") (name "/ONE_WIRE") (class "Default")
      (node (ref "I/O_6") (pin "DQ") (pinfunction "DQ_DQ") (pintype "passive"))
      (node (ref "IC2") (pin "15") (pinfunction "PB1_(D9)_OC1A_15") (pintype "bidirectional"))
      (node (ref "R9") (pin "1") (pinfunction "1_1") (pintype "passive"))
      (node (ref "Y1") (pin "D") (pinfunction "DQ_D") (pintype "passive"))
    )
    (net (code "21") (name "/PWM_DRIVE_1") (class "Default")
      (node (ref "FAN1") (pin "4") (pinfunction "PWM_4") (pintype "passive"))
      (node (ref "FAN2") (pin "4") (pinfunction "PWM_4") (pintype "passive"))
      (node (ref "FAN3") (pin "4") (pinfunction "PWM_4") (pintype "passive"))
      (node (ref "FAN4") (pin "4") (pinfunction "PWM_4") (pintype "passive"))
      (node (ref "IC2") (pin "16") (pinfunction "PB2_(D10)_OC1B_16") (pintype "bidirectional"))
    )
    (net (code "22") (name "/PWM_DRIVE_2") (class "Default")
      (node (ref "FAN5") (pin "4") (pinfunction "PWM_4") (pintype "passive"))
      (node (ref "FAN6") (pin "4") (pinfunction "PWM_4") (pintype "passive"))
      (node (ref "IC2") (pin "5") (pinfunction "PD3_(D3)_OC2B_5") (pintype "bidirectional"))
    )
    (net (code "23") (name "/SYSTEM_CONTROL") (class "Default")
      (node (ref "IC2") (pin "19") (pinfunction "PB5_(D13)_SCK_19") (pintype "bidirectional"))
      (node (ref "S1") (pin "1") (pinfunction "1_1") (pintype "passive"))
    )
    (net (code "24") (name "/SYSTEM_MODE") (class "Default")
      (node (ref "I/O_1") (pin "SYSTEM_MODE+") (pinfunction "SYS_MODE+_SYSTEM_MODE+") (pintype "passive"))
      (node (ref "IC1") (pin "14") (pinfunction "PB0_(D8)_14") (pintype "bidirectional"))
    )
    (net (code "25") (name "/SYSTEM_MODE_LED") (class "Default")
      (node (ref "I/O_1") (pin "SYSTEM_LED+") (pinfunction "SYS_LED+_SYSTEM_LED+") (pintype "passive"))
      (node (ref "IC1") (pin "13") (pinfunction "PD7_(D7)_13") (pintype "bidirectional"))
    )
    (net (code "26") (name "/TEMP_AN1") (class "Default")
      (node (ref "I/O_1") (pin "TEMP_AN1_A") (pinfunction "TEMP_AN1_A_TEMP_AN1_A") (pintype "passive"))
      (node (ref "IC2") (pin "23") (pinfunction "PC0_(A0)_ADC0_23") (pintype "bidirectional"))
      (node (ref "R23") (pin "1") (pinfunction "1_1") (pintype "passive"))
    )
    (net (code "27") (name "/TEMP_AN2") (class "Default")
      (node (ref "I/O_1") (pin "TEMP_AN2_A") (pinfunction "TEMP_AN2_A_TEMP_AN2_A") (pintype "passive"))
      (node (ref "IC2") (pin "26") (pinfunction "PC3_(A3)_ADC3_26") (pintype "bidirectional"))
      (node (ref "R26") (pin "1") (pinfunction "1_1") (pintype "passive"))
    )
    (net (code "28") (name "/VCC_DRIVE_1") (class "Default")
      (node (ref "IC1") (pin "16") (pinfunction "PB2_(D10)_OC1B_16") (pintype "bidirectional"))
      (node (ref "IC4") (pin "2") (pinfunction "2_2") (pintype "passive"))
    )
    (net (code "29") (name "/VCC_DRIVE_2") (class "Default")
      (node (ref "IC1") (pin "5") (pinfunction "PD3_(D3)_OC2B_5") (pintype "bidirectional"))
      (node (ref "IC3") (pin "2") (pinfunction "2_2") (pintype "passive"))
    )
    (net (code "30") (name "Net-(C7-Pad2)") (class "Default")
      (node (ref "C7") (pin "2") (pinfunction "2_2") (pintype "passive"))
      (node (ref "I/O_2") (pin "RST") (pinfunction "RST_RST") (pintype "passive"))
    )
    (net (code "31") (name "Net-(C14-Pad1)") (class "Default")
      (node (ref "C14") (pin "1") (pinfunction "1_1") (pintype "passive"))
      (node (ref "I/O_3") (pin "RST") (pinfunction "RST_RST") (pintype "passive"))
    )
    (net (code "32") (name "Net-(C16-Pad1)") (class "Default")
      (node (ref "C16") (pin "1") (pinfunction "1_1") (pintype "passive"))
      (node (ref "F2") (pin "2") (pinfunction "2_2") (pintype "passive"))
      (node (ref "V1") (pin "VI") (pinfunction "VI_VI") (pintype "input"))
    )
    (net (code "33") (name "Net-(D1-PadC)") (class "Default")
      (node (ref "D1") (pin "C") (pinfunction "C_C") (pintype "passive"))
      (node (ref "F2") (pin "1") (pinfunction "1_1") (pintype "passive"))
    )
    (net (code "34") (name "Net-(D2-PadC)") (class "Default")
      (node (ref "D2") (pin "C") (pinfunction "C_C") (pintype "passive"))
      (node (ref "M1") (pin "G") (pinfunction "G_G") (pintype "passive"))
      (node (ref "R27") (pin "1") (pinfunction "1_1") (pintype "passive"))
    )
    (net (code "35") (name "Net-(D9-PadA)") (class "Default")
      (node (ref "D9") (pin "A") (pinfunction "A_A") (pintype "passive"))
      (node (ref "Q1") (pin "G") (pinfunction "G_G") (pintype "passive"))
      (node (ref "R1") (pin "1") (pinfunction "1_1") (pintype "passive"))
    )
    (net (code "36") (name "Net-(D10-PadA)") (class "Default")
      (node (ref "D10") (pin "A") (pinfunction "A_A") (pintype "passive"))
      (node (ref "Q2") (pin "G") (pinfunction "G_G") (pintype "passive"))
      (node (ref "R2") (pin "1") (pinfunction "1_1") (pintype "passive"))
    )
    (net (code "37") (name "Net-(FUSE-C)") (class "Default")
      (node (ref "FUSE") (pin "K") (pinfunction "C_K") (pintype "passive"))
      (node (ref "M1") (pin "S") (pinfunction "S_S") (pintype "passive"))
    )
    (net (code "38") (name "Net-(I/O_2-PadCTS)") (class "Default")
      (node (ref "I/O_2") (pin "CTS") (pinfunction "CTS_CTS") (pintype "passive"))
      (node (ref "R15") (pin "2") (pinfunction "2_2") (pintype "passive"))
    )
    (net (code "39") (name "Net-(I/O_2-PadTX)") (class "Default")
      (node (ref "I/O_2") (pin "TX") (pinfunction "TX_TX") (pintype "passive"))
      (node (ref "R17") (pin "1") (pinfunction "1_1") (pintype "passive"))
    )
    (net (code "40") (name "Net-(I/O_3-PadCTS)") (class "Default")
      (node (ref "I/O_3") (pin "CTS") (pinfunction "CTS_CTS") (pintype "passive"))
      (node (ref "R16") (pin "1") (pinfunction "1_1") (pintype "passive"))
    )
    (net (code "41") (name "Net-(I/O_3-PadTX)") (class "Default")
      (node (ref "I/O_3") (pin "TX") (pinfunction "TX_TX") (pintype "passive"))
      (node (ref "R18") (pin "1") (pinfunction "1_1") (pintype "passive"))
    )
    (net (code "42") (name "Net-(IC1-AREF)") (class "Default")
      (node (ref "C11") (pin "1") (pinfunction "1_1") (pintype "passive"))
      (node (ref "IC1") (pin "21") (pinfunction "AREF_21") (pintype "bidirectional"))
    )
    (net (code "43") (name "Net-(IC1-AVCC)") (class "Default")
      (node (ref "C10") (pin "1") (pinfunction "1_1") (pintype "passive"))
      (node (ref "I/O_4") (pin "VCC") (pinfunction "VCC_VCC") (pintype "passive"))
      (node (ref "IC1") (pin "20") (pinfunction "AVCC_20") (pintype "bidirectional"))
      (node (ref "L2") (pin "1") (pinfunction "1_1") (pintype "passive"))
    )
    (net (code "44") (name "Net-(IC1-PB6_XTAL1)") (class "Default")
      (node (ref "C3") (pin "1") (pinfunction "1_1") (pintype "passive"))
      (node (ref "IC1") (pin "9") (pinfunction "PB6_XTAL1_9") (pintype "bidirectional"))
      (node (ref "T1") (pin "1") (pinfunction "1_1") (pintype "passive"))
    )
    (net (code "45") (name "Net-(IC1-PB7_XTAL2)") (class "Default")
      (node (ref "C4") (pin "1") (pinfunction "1_1") (pintype "passive"))
      (node (ref "IC1") (pin "10") (pinfunction "PB7_XTAL2_10") (pintype "bidirectional"))
      (node (ref "T1") (pin "2") (pinfunction "2_2") (pintype "passive"))
    )
    (net (code "46") (name "Net-(IC1-PC6_RESET)") (class "Default")
      (node (ref "C7") (pin "1") (pinfunction "1_1") (pintype "passive"))
      (node (ref "D3") (pin "A") (pinfunction "A_A") (pintype "passive"))
      (node (ref "IC1") (pin "1") (pinfunction "PC6_RESET_1") (pintype "bidirectional"))
      (node (ref "R21") (pin "1") (pinfunction "1_1") (pintype "passive"))
    )
    (net (code "47") (name "Net-(IC1-PD0_(D0)_USB_RX)") (class "Default")
      (node (ref "IC1") (pin "2") (pinfunction "PD0_(D0)_USB_RX_2") (pintype "bidirectional"))
      (node (ref "N2") (pin "G") (pinfunction "G_G") (pintype "passive"))
      (node (ref "R17") (pin "2") (pinfunction "2_2") (pintype "passive"))
    )
    (net (code "48") (name "Net-(IC1-PD1_(D1)_USB_TX)") (class "Default")
      (node (ref "I/O_2") (pin "RX") (pinfunction "RX_RX") (pintype "passive"))
      (node (ref "IC1") (pin "3") (pinfunction "PD1_(D1)_USB_TX_3") (pintype "bidirectional"))
      (node (ref "N1") (pin "G") (pinfunction "G_G") (pintype "passive"))
    )
    (net (code "49") (name "Net-(IC2-AREF)") (class "Default")
      (node (ref "C13") (pin "1") (pinfunction "1_1") (pintype "passive"))
      (node (ref "IC2") (pin "21") (pinfunction "AREF_21") (pintype "bidirectional"))
    )
    (net (code "50") (name "Net-(IC2-AVCC)") (class "Default")
      (node (ref "C12") (pin "1") (pinfunction "1_1") (pintype "passive"))
      (node (ref "IC2") (pin "20") (pinfunction "AVCC_20") (pintype "bidirectional"))
      (node (ref "L1") (pin "1") (pinfunction "1_1") (pintype "passive"))
    )
    (net (code "51") (name "Net-(IC2-PB6_XTAL1)") (class "Default")
      (node (ref "C2") (pin "1") (pinfunction "1_1") (pintype "passive"))
      (node (ref "IC2") (pin "9") (pinfunction "PB6_XTAL1_9") (pintype "bidirectional"))
      (node (ref "T2") (pin "2") (pinfunction "2_2") (pintype "passive"))
    )
    (net (code "52") (name "Net-(IC2-PB7_XTAL2)") (class "Default")
      (node (ref "C1") (pin "1") (pinfunction "1_1") (pintype "passive"))
      (node (ref "IC2") (pin "10") (pinfunction "PB7_XTAL2_10") (pintype "bidirectional"))
      (node (ref "T2") (pin "1") (pinfunction "1_1") (pintype "passive"))
    )
    (net (code "53") (name "Net-(IC2-PC6_RESET)") (class "Default")
      (node (ref "C14") (pin "2") (pinfunction "2_2") (pintype "passive"))
      (node (ref "D4") (pin "A") (pinfunction "A_A") (pintype "passive"))
      (node (ref "IC2") (pin "1") (pinfunction "PC6_RESET_1") (pintype "bidirectional"))
      (node (ref "R22") (pin "1") (pinfunction "1_1") (pintype "passive"))
    )
    (net (code "54") (name "Net-(IC2-PD0_(D0)_USB_RX)") (class "Default")
      (node (ref "IC2") (pin "2") (pinfunction "PD0_(D0)_USB_RX_2") (pintype "bidirectional"))
      (node (ref "R18") (pin "2") (pinfunction "2_2") (pintype "passive"))
    )
    (net (code "55") (name "Net-(IC2-PD1_(D1)_USB_TX)") (class "Default")
      (node (ref "I/O_3") (pin "RX") (pinfunction "RX_RX") (pintype "passive"))
      (node (ref "IC2") (pin "3") (pinfunction "PD1_(D1)_USB_TX_3") (pintype "bidirectional"))
    )
    (net (code "56") (name "Net-(IC3-Pad6)") (class "Default")
      (node (ref "IC3") (pin "6") (pinfunction "6_6") (pintype "passive"))
      (node (ref "IC3") (pin "7") (pinfunction "7_7") (pintype "passive"))
      (node (ref "R1") (pin "2") (pinfunction "2_2") (pintype "passive"))
    )
    (net (code "57") (name "Net-(IC4-Pad6)") (class "Default")
      (node (ref "IC4") (pin "6") (pinfunction "6_6") (pintype "passive"))
      (node (ref "IC4") (pin "7") (pinfunction "7_7") (pintype "passive"))
      (node (ref "R2") (pin "2") (pinfunction "2_2") (pintype "passive"))
    )
    (net (code "58") (name "Net-(M1-PadD)") (class "Default")
      (node (ref "M1") (pin "D") (pinfunction "D_D") (pintype "passive"))
      (node (ref "R12") (pin "2") (pinfunction "2_2") (pintype "passive"))
    )
    (net (code "59") (name "Net-(N1-PadD)") (class "Default")
      (node (ref "N1") (pin "D") (pinfunction "D_D") (pintype "passive"))
      (node (ref "R5") (pin "1") (pinfunction "1_1") (pintype "passive"))
      (node (ref "TX") (pin "A") (pinfunction "A_A") (pintype "passive"))
    )
    (net (code "60") (name "Net-(N2-PadD)") (class "Default")
      (node (ref "N2") (pin "D") (pinfunction "D_D") (pintype "passive"))
      (node (ref "R6") (pin "1") (pinfunction "1_1") (pintype "passive"))
      (node (ref "RX") (pin "A") (pinfunction "A_A") (pintype "passive"))
    )
    (net (code "61") (name "Net-(P1-S)") (class "Default")
      (node (ref "P1") (pin "2") (pinfunction "S_2") (pintype "passive"))
      (node (ref "R4") (pin "2") (pinfunction "2_2") (pintype "passive"))
    )
    (net (code "62") (name "Net-(P2-S)") (class "Default")
      (node (ref "P2") (pin "2") (pinfunction "S_2") (pintype "passive"))
      (node (ref "R3") (pin "2") (pinfunction "2_2") (pintype "passive"))
    )
    (net (code "63") (name "Net-(POWER-12V_1)") (class "Default")
      (node (ref "F1") (pin "1") (pinfunction "1_1") (pintype "passive"))
      (node (ref "FUSE") (pin "A") (pinfunction "A_A") (pintype "passive"))
      (node (ref "POWER") (pin "1") (pinfunction "12V_1_1") (pintype "passive"))
      (node (ref "POWER") (pin "2") (pinfunction "12V_2_2") (pintype "passive"))
      (node (ref "PWR") (pin "A") (pinfunction "A_A") (pintype "passive"))
    )
    (net (code "64") (name "Net-(PWR-C)") (class "Default")
      (node (ref "PWR") (pin "K") (pinfunction "C_K") (pintype "passive"))
      (node (ref "R13") (pin "2") (pinfunction "2_2") (pintype "passive"))
    )
    (net (code "65") (name "Net-(R20-Pad2)") (class "Default")
      (node (ref "R20") (pin "2") (pinfunction "2_2") (pintype "passive"))
      (node (ref "S3") (pin "3") (pinfunction "3_3") (pintype "passive"))
    )
    (net (code "66") (name "Net-(R24-Pad1)") (class "Default")
      (node (ref "R24") (pin "1") (pinfunction "1_1") (pintype "passive"))
      (node (ref "S1") (pin "3") (pinfunction "3_3") (pintype "passive"))
    )
    (net (code "67") (name "Net-(R25-Pad1)") (class "Default")
      (node (ref "R25") (pin "1") (pinfunction "1_1") (pintype "passive"))
      (node (ref "S2") (pin "3") (pinfunction "3_3") (pintype "passive"))
    )
  )
)
